# POWER.net
KiCad netlist of a schematic drawn in Altium Designer
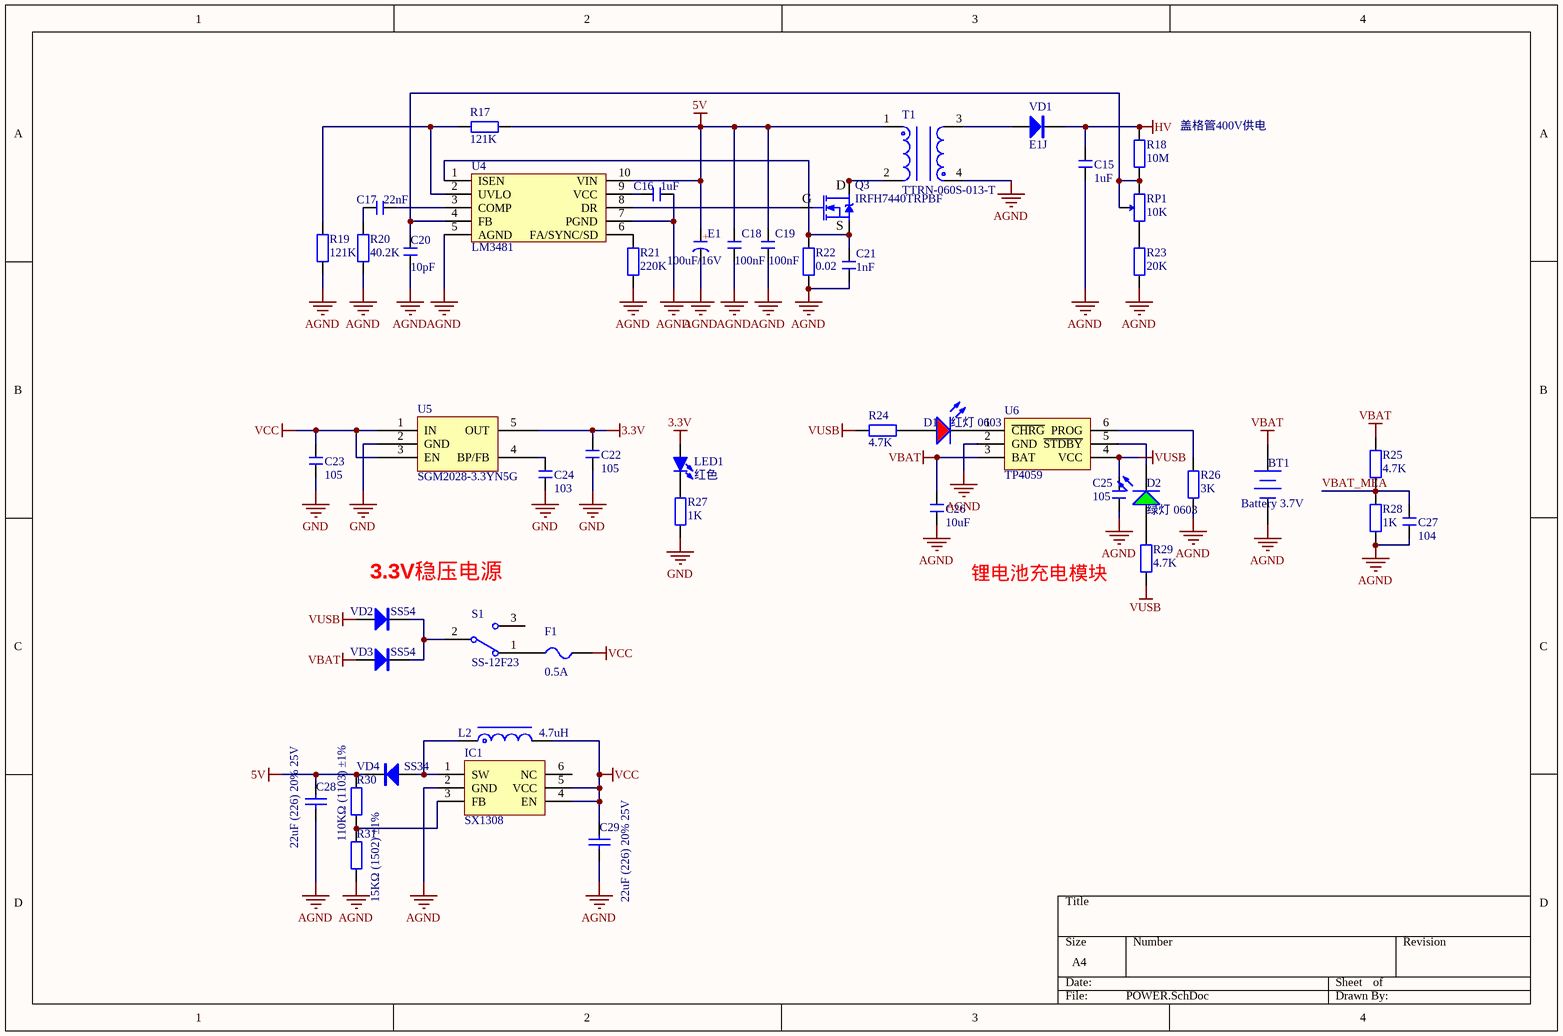
[diagram p0: POWER.SchDoc]

(export (version "E")
  (design (tool "Eeschema 10.0.6"))
  (components
    (comp (ref "BT1")
      (value "Battery 3.7V")
      (footprint "BAT-2")
      (description "Multicell Battery")
      (fields (field (name "PUBLISHER") "Altium Limited"))
      (libsource (lib "LIB") (part "Battery"))
    )
    (comp (ref "C15")
      (value "1uF")
      (footprint "C 1812")
      (description "无极性贴片电容")
      (fields (field (name "版权归属") "源创客"))
      (libsource (lib "电阻-电容-电感") (part "C"))
    )
    (comp (ref "C16")
      (value "1uF")
      (footprint "C 0603")
      (description "无极性贴片电容")
      (fields (field (name "版权归属") "源创客"))
      (libsource (lib "电阻-电容-电感") (part "C"))
    )
    (comp (ref "C17")
      (value "22nF")
      (footprint "C 0603")
      (description "无极性贴片电容")
      (fields (field (name "版权归属") "源创客"))
      (libsource (lib "电阻-电容-电感") (part "C"))
    )
    (comp (ref "C18")
      (value "100nF")
      (footprint "C 0603")
      (description "无极性贴片电容")
      (fields (field (name "版权归属") "源创客"))
      (libsource (lib "电阻-电容-电感") (part "C"))
    )
    (comp (ref "C19")
      (value "100nF")
      (footprint "C 0603")
      (description "无极性贴片电容")
      (fields (field (name "版权归属") "源创客"))
      (libsource (lib "电阻-电容-电感") (part "C"))
    )
    (comp (ref "C20")
      (value "10pF")
      (footprint "C 0603")
      (description "无极性贴片电容")
      (fields (field (name "版权归属") "源创客"))
      (libsource (lib "电阻-电容-电感") (part "C"))
    )
    (comp (ref "C21")
      (value "1nF")
      (footprint "C 0603")
      (description "无极性贴片电容")
      (fields (field (name "版权归属") "源创客"))
      (libsource (lib "电阻-电容-电感") (part "C"))
    )
    (comp (ref "C22")
      (value "105")
      (footprint "C 0603")
      (description "无极性贴片电容")
      (fields (field (name "版权归属") "源创客"))
      (libsource (lib "电阻-电容-电感") (part "C"))
    )
    (comp (ref "C23")
      (value "105")
      (footprint "C 0603")
      (description "无极性贴片电容")
      (fields (field (name "版权归属") "源创客"))
      (libsource (lib "电阻-电容-电感") (part "C"))
    )
    (comp (ref "C24")
      (value "103")
      (footprint "C 0603")
      (description "无极性贴片电容")
      (fields (field (name "版权归属") "源创客"))
      (libsource (lib "电阻-电容-电感") (part "C"))
    )
    (comp (ref "C25")
      (value "105")
      (footprint "C 0603")
      (description "无极性贴片电容")
      (fields (field (name "版权归属") "源创客"))
      (libsource (lib "电阻-电容-电感") (part "C"))
    )
    (comp (ref "C26")
      (value "10uF")
      (footprint "C 0805")
      (description "无极性贴片电容")
      (fields (field (name "版权归属") "源创客"))
      (libsource (lib "电阻-电容-电感") (part "C"))
    )
    (comp (ref "C27")
      (value "104")
      (footprint "C 0603")
      (description "无极性贴片电容")
      (fields (field (name "版权归属") "源创客"))
      (libsource (lib "电阻-电容-电感") (part "C"))
    )
    (comp (ref "C28")
      (value "22uF (226) 20% 25V")
      (footprint "0805_C")
      (description "贴片电容")
      (libsource (lib "Miscellaneous Devices LC") (part "0805 22uF (226) 20% 25V"))
    )
    (comp (ref "C29")
      (value "22uF (226) 20% 25V")
      (footprint "0805_C")
      (description "贴片电容")
      (libsource (lib "Miscellaneous Devices LC") (part "0805 22uF (226) 20% 25V"))
    )
    (comp (ref "D1")
      (value "红灯 0603")
      (footprint "0603_LED_S1")
      (description "发光二极管")
      (libsource (lib "Miscellaneous Devices LC") (part "0603 红灯"))
    )
    (comp (ref "D2")
      (value "绿灯 0603")
      (footprint "0603_LED_S1")
      (description "发光二极管")
      (libsource (lib "Miscellaneous Devices LC") (part "0603 绿灯"))
    )
    (comp (ref "E1")
      (value "100uF/16V")
      (footprint "CM D(6.3*5.4)")
      (description "贴片电解电容")
      (fields (field (name "版权归属") "源创客"))
      (libsource (lib "电阻-电容-电感") (part "C-CM"))
    )
    (comp (ref "F1")
      (value "0.5A")
      (footprint "FU 0805")
      (description "贴片保险丝")
      (fields (field (name "版权归属") "源创客"))
      (libsource (lib "保险丝-晶振") (part "FU"))
    )
    (comp (ref "IC1")
      (value "SX1308")
      (footprint "SOT23-6N")
      (description "可调升压芯片")
      (libsource (lib "1.1 - 电源类芯片") (part "SX1308"))
    )
    (comp (ref "L2")
      (value "4.7uH")
      (footprint "L 04020")
      (description "功率屏蔽电感")
      (fields (field (name "版权归属") "源创客"))
      (libsource (lib "电阻-电容-电感") (part "L-CDRH"))
    )
    (comp (ref "LED1")
      (value "红色")
      (footprint "LED 0603W")
      (description "贴片LED")
      (fields (field (name "版权归属") "源创客"))
      (libsource (lib "LED") (part "LED-SMD"))
    )
    (comp (ref "Q3")
      (value "IRFH7440TRPBF")
      (footprint "PQFN8_5X6_B_INF")
      (description "40V/159A N沟道MOS管")
      (libsource (lib "场效应管-可控硅") (part "IRFH7440TRPBF"))
    )
    (comp (ref "R17")
      (value "121K")
      (footprint "R 0603")
      (description "贴片电阻")
      (fields (field (name "版权归属") "源创客"))
      (libsource (lib "电阻-电容-电感") (part "R"))
    )
    (comp (ref "R18")
      (value "10M")
      (footprint "R 0603")
      (description "贴片电阻")
      (fields (field (name "版权归属") "源创客"))
      (libsource (lib "电阻-电容-电感") (part "R"))
    )
    (comp (ref "R19")
      (value "121K")
      (footprint "R 0603")
      (description "贴片电阻")
      (fields (field (name "版权归属") "源创客"))
      (libsource (lib "电阻-电容-电感") (part "R"))
    )
    (comp (ref "R20")
      (value "40.2K")
      (footprint "R 0603")
      (description "贴片电阻")
      (fields (field (name "版权归属") "源创客"))
      (libsource (lib "电阻-电容-电感") (part "R"))
    )
    (comp (ref "R21")
      (value "220K")
      (footprint "R 0603")
      (description "贴片电阻")
      (fields (field (name "版权归属") "源创客"))
      (libsource (lib "电阻-电容-电感") (part "R"))
    )
    (comp (ref "R22")
      (value "0.02")
      (footprint "R 0805")
      (description "贴片电阻")
      (fields (field (name "版权归属") "源创客"))
      (libsource (lib "电阻-电容-电感") (part "R"))
    )
    (comp (ref "R23")
      (value "20K")
      (footprint "R 0603")
      (description "贴片电阻")
      (fields (field (name "版权归属") "源创客"))
      (libsource (lib "电阻-电容-电感") (part "R"))
    )
    (comp (ref "R24")
      (value "4.7K")
      (footprint "R 0603")
      (description "贴片电阻")
      (fields (field (name "版权归属") "源创客"))
      (libsource (lib "电阻-电容-电感") (part "R"))
    )
    (comp (ref "R25")
      (value "4.7K")
      (footprint "R 0603")
      (description "贴片电阻")
      (fields (field (name "版权归属") "源创客"))
      (libsource (lib "电阻-电容-电感") (part "R"))
    )
    (comp (ref "R26")
      (value "3K")
      (footprint "R 0603")
      (description "贴片电阻")
      (fields (field (name "版权归属") "源创客"))
      (libsource (lib "电阻-电容-电感") (part "R"))
    )
    (comp (ref "R27")
      (value "1K")
      (footprint "R 0603")
      (description "贴片电阻")
      (fields (field (name "版权归属") "源创客"))
      (libsource (lib "电阻-电容-电感") (part "R"))
    )
    (comp (ref "R28")
      (value "1K")
      (footprint "R 0603")
      (description "贴片电阻")
      (fields (field (name "版权归属") "源创客"))
      (libsource (lib "电阻-电容-电感") (part "R"))
    )
    (comp (ref "R29")
      (value "4.7K")
      (footprint "R 0603")
      (description "贴片电阻")
      (fields (field (name "版权归属") "源创客"))
      (libsource (lib "电阻-电容-电感") (part "R"))
    )
    (comp (ref "R30")
      (value "110KΩ (1103) ±1%")
      (footprint "0603_R")
      (description "贴片电阻")
      (libsource (lib "Miscellaneous Devices LC") (part "0603 110KΩ (1103) 1%"))
    )
    (comp (ref "R31")
      (value "15KΩ (1502) ±1%")
      (footprint "0603_R")
      (description "贴片电阻")
      (libsource (lib "Miscellaneous Devices LC") (part "0603 15KΩ (1502) 1%"))
    )
    (comp (ref "RP1")
      (value "10K")
      (footprint "3303W")
      (description "贴片电位器")
      (fields (field (name "版权归属") "源创客"))
      (libsource (lib "电阻-电容-电感") (part "RP-SMD"))
    )
    (comp (ref "S1")
      (value "SS-12F23")
      (footprint "SS-12D07")
      (description "1路拨动开关")
      (fields (field (name "版权归属") "源创客"))
      (libsource (lib "按键-开关") (part "SSW-1P"))
    )
    (comp (ref "T1")
      (value "TTRN-060S-013-T")
      (footprint "EE5.0")
      (description "1:10.5 3.2A 贴片闪光灯变压器")
      (libsource (lib "变压器") (part "TTRN-060S-013-T"))
    )
    (comp (ref "U4")
      (value "LM3481")
      (footprint "VSSOP10")
      (description "High-Efficiency Controller for Boost, SEPIC and Flyback DC-DC Converters")
      (libsource (lib "IC芯片") (part "LM3481"))
    )
    (comp (ref "U5")
      (value "SGM2028-3.3YN5G")
      (footprint "SOT23-5")
      (description "500mA,3.3V低压差线性稳压器")
      (libsource (lib "LIB") (part "SGM2028-3.3YN5G"))
    )
    (comp (ref "U6")
      (value "TP4059")
      (footprint "SOT23-6_N")
      (description "600mA单节锂电池充电芯片")
      (libsource (lib "LIB") (part "TP4059"))
    )
    (comp (ref "VD1")
      (value "E1J")
      (footprint "SOD-123F")
      (description "600V/1A 超快恢复二极管")
      (libsource (lib "二极管-整流桥") (part "E1J"))
    )
    (comp (ref "VD2")
      (value "SS54")
      (footprint "SMA")
      (description "肖特基二极管")
      (fields (field (name "版权归属") "源创客"))
      (libsource (lib "二极管-整流桥") (part "SS14"))
    )
    (comp (ref "VD3")
      (value "SS54")
      (footprint "SMA")
      (description "肖特基二极管")
      (fields (field (name "版权归属") "源创客"))
      (libsource (lib "二极管-整流桥") (part "SS14"))
    )
    (comp (ref "VD4")
      (value "SS34")
      (footprint "SMA")
      (description "肖特基二极管")
      (fields (field (name "版权归属") "源创客"))
      (libsource (lib "二极管-整流桥") (part "SS14"))
    )
  )
  (nets
    (net (code "1") (name "/VBAT_MEA") (class "Default")
      (node (ref "C27") (pin "2") (pinfunction "2_2") (pintype "passive"))
      (node (ref "R25") (pin "1") (pinfunction "1_1") (pintype "passive"))
      (node (ref "R28") (pin "2") (pinfunction "2_2") (pintype "passive"))
    )
    (net (code "2") (name "3.3V") (class "Default")
      (node (ref "C22") (pin "2") (pinfunction "2_2") (pintype "passive"))
      (node (ref "LED1") (pin "1") (pinfunction "A_1") (pintype "passive"))
      (node (ref "U5") (pin "5") (pinfunction "OUT_5") (pintype "passive"))
    )
    (net (code "3") (name "5V") (class "Default")
      (node (ref "C18") (pin "2") (pinfunction "2_2") (pintype "passive"))
      (node (ref "C19") (pin "2") (pinfunction "2_2") (pintype "passive"))
      (node (ref "C28") (pin "2") (pinfunction "2_2") (pintype "passive"))
      (node (ref "E1") (pin "1") (pinfunction "A_1") (pintype "passive"))
      (node (ref "R17") (pin "1") (pinfunction "1_1") (pintype "passive"))
      (node (ref "R30") (pin "2") (pinfunction "2_2") (pintype "passive"))
      (node (ref "T1") (pin "1") (pinfunction "1_1") (pintype "passive"))
      (node (ref "U4") (pin "10") (pinfunction "VIN_10") (pintype "passive"))
      (node (ref "VD4") (pin "2") (pinfunction "K_2") (pintype "passive"))
    )
    (net (code "4") (name "AGND") (class "Default")
      (node (ref "BT1") (pin "2") (pinfunction "-_2") (pintype "passive"))
      (node (ref "C15") (pin "1") (pinfunction "1_1") (pintype "passive"))
      (node (ref "C16") (pin "2") (pinfunction "2_2") (pintype "passive"))
      (node (ref "C18") (pin "1") (pinfunction "1_1") (pintype "passive"))
      (node (ref "C19") (pin "1") (pinfunction "1_1") (pintype "passive"))
      (node (ref "C20") (pin "1") (pinfunction "1_1") (pintype "passive"))
      (node (ref "C21") (pin "1") (pinfunction "1_1") (pintype "passive"))
      (node (ref "C25") (pin "1") (pinfunction "1_1") (pintype "passive"))
      (node (ref "C26") (pin "1") (pinfunction "1_1") (pintype "passive"))
      (node (ref "C27") (pin "1") (pinfunction "1_1") (pintype "passive"))
      (node (ref "C28") (pin "1") (pinfunction "1_1") (pintype "passive"))
      (node (ref "C29") (pin "1") (pinfunction "1_1") (pintype "passive"))
      (node (ref "E1") (pin "2") (pinfunction "K_2") (pintype "passive"))
      (node (ref "IC1") (pin "2") (pinfunction "GND_2") (pintype "passive"))
      (node (ref "R19") (pin "1") (pinfunction "1_1") (pintype "passive"))
      (node (ref "R20") (pin "1") (pinfunction "1_1") (pintype "passive"))
      (node (ref "R21") (pin "1") (pinfunction "1_1") (pintype "passive"))
      (node (ref "R22") (pin "1") (pinfunction "1_1") (pintype "passive"))
      (node (ref "R23") (pin "1") (pinfunction "1_1") (pintype "passive"))
      (node (ref "R26") (pin "2") (pinfunction "2_2") (pintype "passive"))
      (node (ref "R28") (pin "1") (pinfunction "1_1") (pintype "passive"))
      (node (ref "R31") (pin "1") (pinfunction "1_1") (pintype "passive"))
      (node (ref "T1") (pin "4") (pinfunction "4_4") (pintype "passive"))
      (node (ref "U4") (pin "5") (pinfunction "AGND_5") (pintype "passive"))
      (node (ref "U4") (pin "7") (pinfunction "PGND_7") (pintype "passive"))
      (node (ref "U6") (pin "2") (pinfunction "GND_2") (pintype "passive"))
    )
    (net (code "5") (name "GND") (class "Default")
      (node (ref "C22") (pin "1") (pinfunction "1_1") (pintype "passive"))
      (node (ref "C23") (pin "1") (pinfunction "1_1") (pintype "passive"))
      (node (ref "C24") (pin "2") (pinfunction "2_2") (pintype "passive"))
      (node (ref "R27") (pin "2") (pinfunction "2_2") (pintype "passive"))
      (node (ref "U5") (pin "2") (pinfunction "GND_2") (pintype "passive"))
    )
    (net (code "6") (name "HV") (class "Default")
      (node (ref "C15") (pin "2") (pinfunction "2_2") (pintype "passive"))
      (node (ref "R18") (pin "2") (pinfunction "2_2") (pintype "passive"))
      (node (ref "VD1") (pin "2") (pinfunction "K_2") (pintype "passive"))
    )
    (net (code "7") (name "Net-(C17-Pad1)") (class "Default")
      (node (ref "C17") (pin "1") (pinfunction "1_1") (pintype "passive"))
      (node (ref "R20") (pin "2") (pinfunction "2_2") (pintype "passive"))
    )
    (net (code "8") (name "Net-(D1-PadA)") (class "Default")
      (node (ref "D1") (pin "A") (pinfunction "A_A") (pintype "passive"))
      (node (ref "R24") (pin "1") (pinfunction "1_1") (pintype "passive"))
    )
    (net (code "9") (name "Net-(D2-PadA)") (class "Default")
      (node (ref "D2") (pin "A") (pinfunction "A_A") (pintype "passive"))
      (node (ref "R29") (pin "1") (pinfunction "1_1") (pintype "passive"))
    )
    (net (code "10") (name "Net-(F1-Pad1)") (class "Default")
      (node (ref "F1") (pin "1") (pinfunction "1_1") (pintype "passive"))
      (node (ref "S1") (pin "1") (pinfunction "1_1") (pintype "passive"))
    )
    (net (code "11") (name "Net-(IC1-FB)") (class "Default")
      (node (ref "IC1") (pin "3") (pinfunction "FB_3") (pintype "passive"))
      (node (ref "R30") (pin "1") (pinfunction "1_1") (pintype "passive"))
      (node (ref "R31") (pin "2") (pinfunction "2_2") (pintype "passive"))
    )
    (net (code "12") (name "Net-(IC1-SW)") (class "Default")
      (node (ref "IC1") (pin "1") (pinfunction "SW_1") (pintype "passive"))
      (node (ref "L2") (pin "1") (pinfunction "1_1") (pintype "passive"))
      (node (ref "VD4") (pin "1") (pinfunction "A_1") (pintype "passive"))
    )
    (net (code "13") (name "Net-(LED1-K)") (class "Default")
      (node (ref "LED1") (pin "2") (pinfunction "K_2") (pintype "passive"))
      (node (ref "R27") (pin "1") (pinfunction "1_1") (pintype "passive"))
    )
    (net (code "14") (name "Net-(Q3-D-Pad5)") (class "Default")
      (node (ref "Q3") (pin "5") (pinfunction "D_5") (pintype "passive"))
      (node (ref "Q3") (pin "6") (pinfunction "D_6") (pintype "passive"))
      (node (ref "Q3") (pin "7") (pinfunction "D_7") (pintype "passive"))
      (node (ref "Q3") (pin "8") (pinfunction "D_8") (pintype "passive"))
      (node (ref "T1") (pin "2") (pinfunction "2_2") (pintype "passive"))
    )
    (net (code "15") (name "Net-(Q3-G)") (class "Default")
      (node (ref "Q3") (pin "4") (pinfunction "G_4") (pintype "passive"))
      (node (ref "U4") (pin "8") (pinfunction "DR_8") (pintype "passive"))
    )
    (net (code "16") (name "Net-(R23-Pad2)") (class "Default")
      (node (ref "R23") (pin "2") (pinfunction "2_2") (pintype "passive"))
      (node (ref "RP1") (pin "3") (pinfunction "3_3") (pintype "passive"))
    )
    (net (code "17") (name "Net-(U4-COMP)") (class "Default")
      (node (ref "C17") (pin "2") (pinfunction "2_2") (pintype "passive"))
      (node (ref "U4") (pin "3") (pinfunction "COMP_3") (pintype "passive"))
    )
    (net (code "18") (name "Net-(U4-FA{slash}SYNC{slash}SD)") (class "Default")
      (node (ref "R21") (pin "2") (pinfunction "2_2") (pintype "passive"))
      (node (ref "U4") (pin "6") (pinfunction "FA/SYNC/SD_6") (pintype "passive"))
    )
    (net (code "19") (name "Net-(U4-FB)") (class "Default")
      (node (ref "C20") (pin "2") (pinfunction "2_2") (pintype "passive"))
      (node (ref "R18") (pin "1") (pinfunction "1_1") (pintype "passive"))
      (node (ref "RP1") (pin "1") (pinfunction "1_1") (pintype "passive"))
      (node (ref "RP1") (pin "2") (pinfunction "2_2") (pintype "passive"))
      (node (ref "U4") (pin "4") (pinfunction "FB_4") (pintype "passive"))
    )
    (net (code "20") (name "Net-(U4-ISEN)") (class "Default")
      (node (ref "C21") (pin "2") (pinfunction "2_2") (pintype "passive"))
      (node (ref "Q3") (pin "1") (pinfunction "S_1") (pintype "passive"))
      (node (ref "Q3") (pin "2") (pinfunction "S_2") (pintype "passive"))
      (node (ref "Q3") (pin "3") (pinfunction "S_3") (pintype "passive"))
      (node (ref "R22") (pin "2") (pinfunction "2_2") (pintype "passive"))
      (node (ref "U4") (pin "1") (pinfunction "ISEN_1") (pintype "passive"))
    )
    (net (code "21") (name "Net-(U4-UVLO)") (class "Default")
      (node (ref "R17") (pin "2") (pinfunction "2_2") (pintype "passive"))
      (node (ref "R19") (pin "2") (pinfunction "2_2") (pintype "passive"))
      (node (ref "U4") (pin "2") (pinfunction "UVLO_2") (pintype "passive"))
    )
    (net (code "22") (name "Net-(U4-VCC)") (class "Default")
      (node (ref "C16") (pin "1") (pinfunction "1_1") (pintype "passive"))
      (node (ref "U4") (pin "9") (pinfunction "VCC_9") (pintype "passive"))
    )
    (net (code "23") (name "Net-(U5-BP{slash}FB)") (class "Default")
      (node (ref "C24") (pin "1") (pinfunction "1_1") (pintype "passive"))
      (node (ref "U5") (pin "4") (pinfunction "BP/FB_4") (pintype "passive"))
    )
    (net (code "24") (name "Net-(U6-PROG)") (class "Default")
      (node (ref "R26") (pin "1") (pinfunction "1_1") (pintype "passive"))
      (node (ref "U6") (pin "6") (pinfunction "PROG_6") (pintype "passive"))
    )
    (net (code "25") (name "Net-(U6-~{CHRG})") (class "Default")
      (node (ref "D1") (pin "K") (pinfunction "K_K") (pintype "passive"))
      (node (ref "U6") (pin "1") (pinfunction "~{CHRG}_1") (pintype "passive"))
    )
    (net (code "26") (name "Net-(U6-~{STDBY})") (class "Default")
      (node (ref "D2") (pin "K") (pinfunction "K_K") (pintype "passive"))
      (node (ref "U6") (pin "5") (pinfunction "~{STDBY}_5") (pintype "passive"))
    )
    (net (code "27") (name "Net-(VD1-A)") (class "Default")
      (node (ref "T1") (pin "3") (pinfunction "3_3") (pintype "passive"))
      (node (ref "VD1") (pin "1") (pinfunction "A_1") (pintype "passive"))
    )
    (net (code "28") (name "Net-(VD2-K)") (class "Default")
      (node (ref "S1") (pin "2") (pinfunction "2_2") (pintype "passive"))
      (node (ref "VD2") (pin "2") (pinfunction "K_2") (pintype "passive"))
      (node (ref "VD3") (pin "2") (pinfunction "K_2") (pintype "passive"))
    )
    (net (code "29") (name "VBAT") (class "Default")
      (node (ref "BT1") (pin "1") (pinfunction "+_1") (pintype "passive"))
      (node (ref "C26") (pin "2") (pinfunction "2_2") (pintype "passive"))
      (node (ref "R25") (pin "2") (pinfunction "2_2") (pintype "passive"))
      (node (ref "U6") (pin "3") (pinfunction "BAT_3") (pintype "passive"))
      (node (ref "VD3") (pin "1") (pinfunction "A_1") (pintype "passive"))
    )
    (net (code "30") (name "VCC") (class "Default")
      (node (ref "C23") (pin "2") (pinfunction "2_2") (pintype "passive"))
      (node (ref "C29") (pin "2") (pinfunction "2_2") (pintype "passive"))
      (node (ref "F1") (pin "2") (pinfunction "2_2") (pintype "passive"))
      (node (ref "IC1") (pin "4") (pinfunction "EN_4") (pintype "passive"))
      (node (ref "IC1") (pin "5") (pinfunction "VCC_5") (pintype "passive"))
      (node (ref "L2") (pin "2") (pinfunction "2_2") (pintype "passive"))
      (node (ref "U5") (pin "1") (pinfunction "IN_1") (pintype "passive"))
      (node (ref "U5") (pin "3") (pinfunction "EN_3") (pintype "passive"))
    )
    (net (code "31") (name "VUSB") (class "Default")
      (node (ref "C25") (pin "2") (pinfunction "2_2") (pintype "passive"))
      (node (ref "R24") (pin "2") (pinfunction "2_2") (pintype "passive"))
      (node (ref "R29") (pin "2") (pinfunction "2_2") (pintype "passive"))
      (node (ref "U6") (pin "4") (pinfunction "VCC_4") (pintype "passive"))
      (node (ref "VD2") (pin "1") (pinfunction "A_1") (pintype "passive"))
    )
    (net (code "32") (name "unconnected-(IC1-NC-Pad6)") (class "Default")
      (node (ref "IC1") (pin "6") (pinfunction "NC_6") (pintype "passive"))
    )
    (net (code "33") (name "unconnected-(S1-Pad3)") (class "Default")
      (node (ref "S1") (pin "3") (pinfunction "3_3") (pintype "passive"))
    )
  )
)
